# Instrument_Cluster.net
KiCad netlist of a schematic drawn in EAGLE
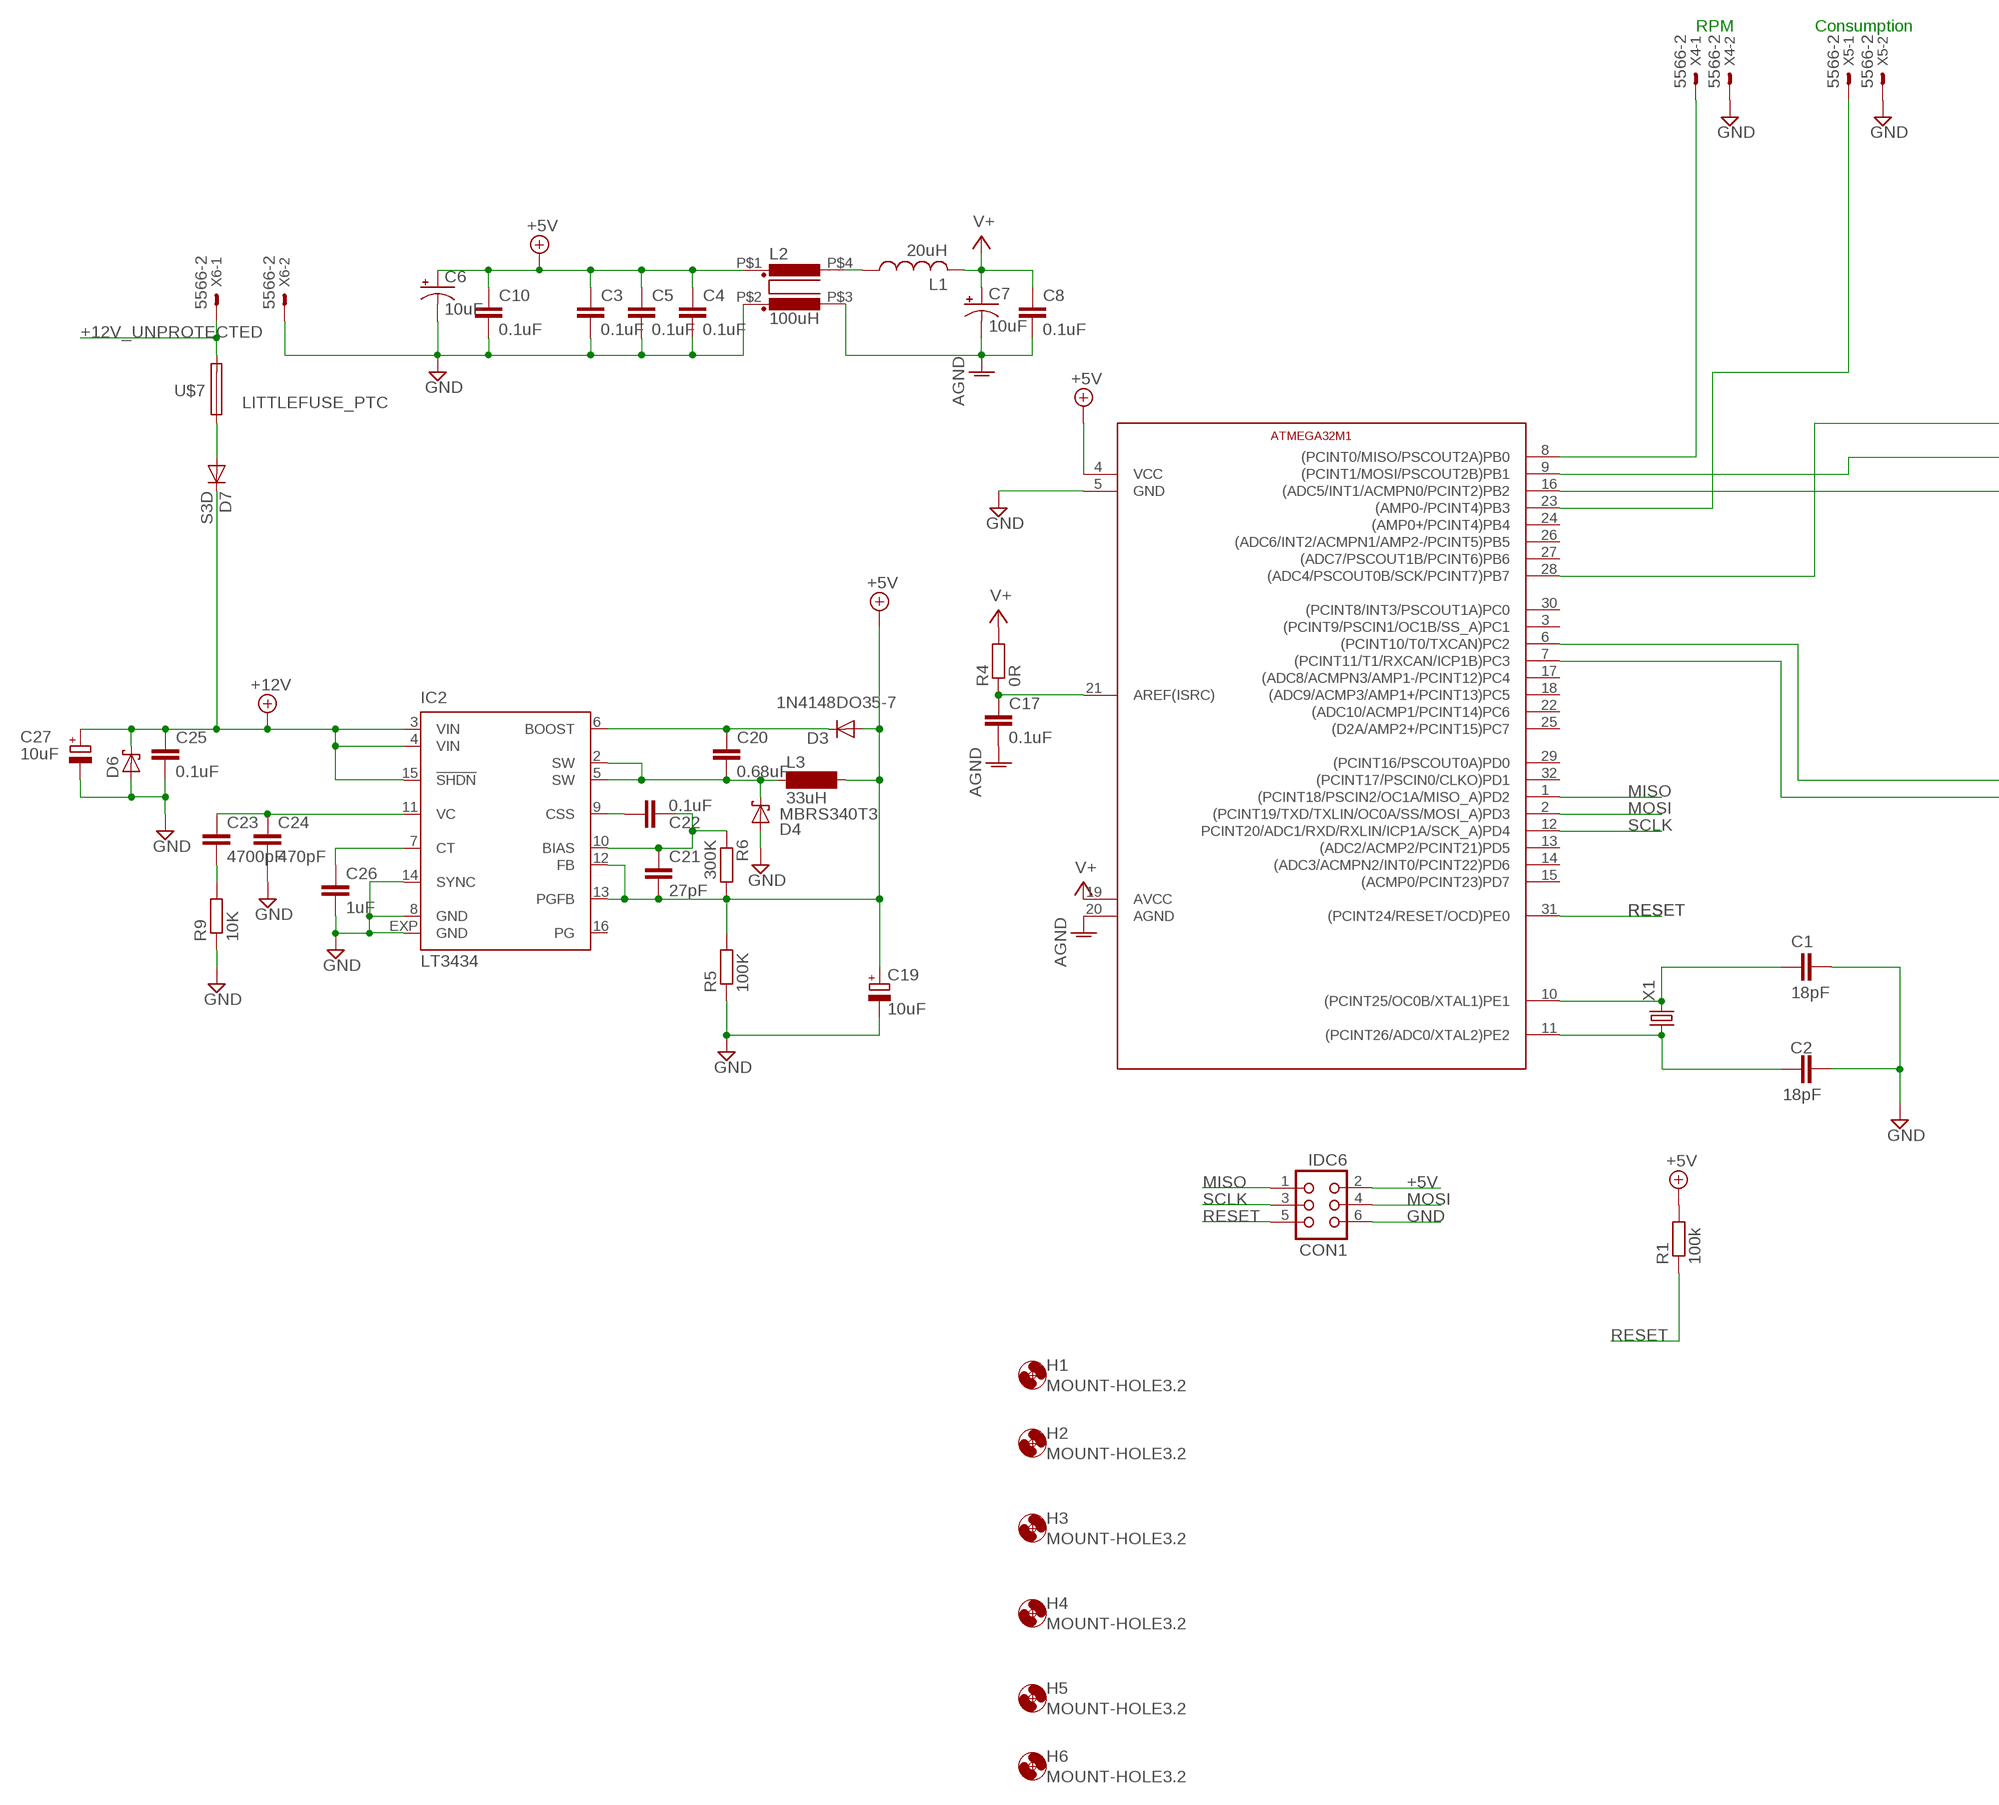
[diagram p0: schematic, sheet 1, part 1 of 2]
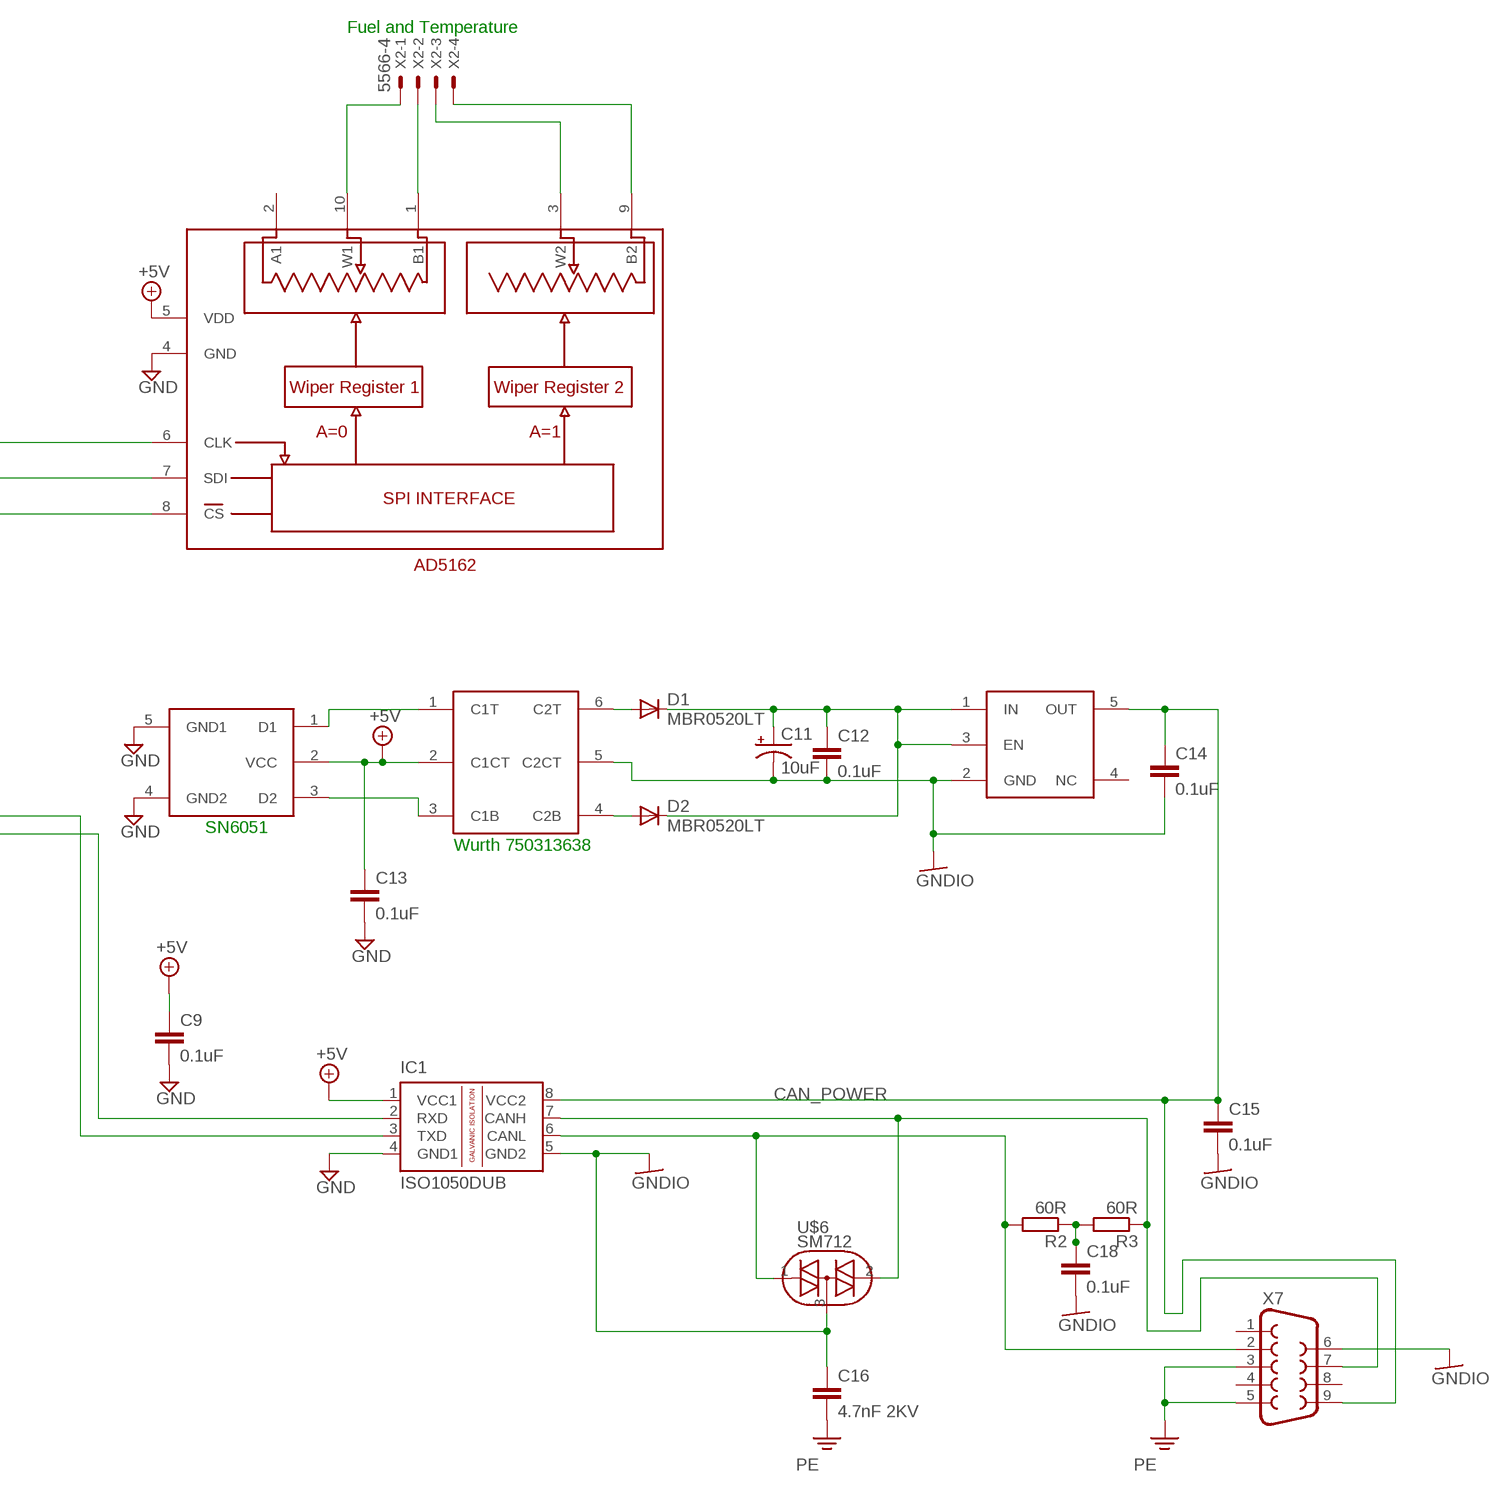
[diagram p1: schematic, sheet 1, part 2 of 2]

(export (version "E")
  (design (tool "Eeschema 10.0.6"))
  (components
    (comp (ref "C1")
      (value "18pF")
      (footprint "eagle-import:C0805")
      (libsource (lib "eagle-import") (part "C-EUC0805"))
    )
    (comp (ref "C2")
      (value "18pF")
      (footprint "eagle-import:C0805")
      (libsource (lib "eagle-import") (part "C-EUC0805"))
    )
    (comp (ref "C3")
      (value "0.1uF")
      (footprint "eagle-import:C0805")
      (libsource (lib "eagle-import") (part "C-EUC0805"))
    )
    (comp (ref "C4")
      (value "0.1uF")
      (footprint "eagle-import:C0805")
      (libsource (lib "eagle-import") (part "C-EUC0805"))
    )
    (comp (ref "C5")
      (value "0.1uF")
      (footprint "eagle-import:C0805")
      (libsource (lib "eagle-import") (part "C-EUC0805"))
    )
    (comp (ref "C6")
      (value "10uF")
      (footprint "eagle-import:SMC_C")
      (libsource (lib "eagle-import") (part "CPOL-USSMCC"))
    )
    (comp (ref "C7")
      (value "10uF")
      (footprint "eagle-import:SMC_C")
      (libsource (lib "eagle-import") (part "CPOL-USSMCC"))
    )
    (comp (ref "C8")
      (value "0.1uF")
      (footprint "eagle-import:C0805")
      (libsource (lib "eagle-import") (part "C-EUC0805"))
    )
    (comp (ref "C9")
      (value "0.1uF")
      (footprint "eagle-import:C0805")
      (libsource (lib "eagle-import") (part "C-EUC0805"))
    )
    (comp (ref "C10")
      (value "0.1uF")
      (footprint "eagle-import:C0805")
      (libsource (lib "eagle-import") (part "C-EUC0805"))
    )
    (comp (ref "C11")
      (value "10uF")
      (footprint "eagle-import:SMC_D")
      (libsource (lib "eagle-import") (part "CPOL-USSMCD"))
    )
    (comp (ref "C12")
      (value "0.1uF")
      (footprint "eagle-import:C0603")
      (libsource (lib "eagle-import") (part "C-EUC0603"))
    )
    (comp (ref "C13")
      (value "0.1uF")
      (footprint "eagle-import:C1206")
      (libsource (lib "eagle-import") (part "C-EUC1206"))
    )
    (comp (ref "C14")
      (value "0.1uF")
      (footprint "eagle-import:C1206")
      (libsource (lib "eagle-import") (part "C-EUC1206"))
    )
    (comp (ref "C15")
      (value "0.1uF")
      (footprint "eagle-import:C0603")
      (libsource (lib "eagle-import") (part "C-EUC0603"))
    )
    (comp (ref "C16")
      (value "4.7nF 2KV")
      (footprint "eagle-import:C1206")
      (libsource (lib "eagle-import") (part "C-EUC1206"))
    )
    (comp (ref "C17")
      (value "0.1uF")
      (footprint "eagle-import:C0805")
      (libsource (lib "eagle-import") (part "C-EUC0805"))
    )
    (comp (ref "C18")
      (value "0.1uF")
      (footprint "eagle-import:C1206")
      (libsource (lib "eagle-import") (part "C-EUC1206"))
    )
    (comp (ref "C19")
      (value "10uF")
      (footprint "eagle-import:SMC_D")
      (libsource (lib "eagle-import") (part "CPOL-EUSMCD"))
    )
    (comp (ref "C20")
      (value "0.68uF")
      (footprint "eagle-import:C0603")
      (libsource (lib "eagle-import") (part "C-EUC0603"))
    )
    (comp (ref "C21")
      (value "27pF")
      (footprint "eagle-import:C0603")
      (libsource (lib "eagle-import") (part "C-EUC0603"))
    )
    (comp (ref "C22")
      (value "0.1uF")
      (footprint "eagle-import:C0603")
      (libsource (lib "eagle-import") (part "C-EUC0603"))
    )
    (comp (ref "C23")
      (value "4700pF")
      (footprint "eagle-import:C0603")
      (libsource (lib "eagle-import") (part "C-EUC0603"))
    )
    (comp (ref "C24")
      (value "470pF")
      (footprint "eagle-import:C0603")
      (libsource (lib "eagle-import") (part "C-EUC0603"))
    )
    (comp (ref "C25")
      (value "0.1uF")
      (footprint "eagle-import:C0603")
      (libsource (lib "eagle-import") (part "C-EUC0603"))
    )
    (comp (ref "C26")
      (value "1uF")
      (footprint "eagle-import:C0603")
      (libsource (lib "eagle-import") (part "C-EUC0603"))
    )
    (comp (ref "C27")
      (value "10uF")
      (footprint "eagle-import:SMC_D")
      (libsource (lib "eagle-import") (part "CPOL-EUSMCD"))
    )
    (comp (ref "CON1")
      (value "IDC6")
      (footprint "eagle-import:CON06")
      (libsource (lib "eagle-import") (part "CON06"))
    )
    (comp (ref "D1")
      (value "MBR0520LT")
      (footprint "eagle-import:SOD123")
      (libsource (lib "eagle-import") (part "MBR0520LT"))
    )
    (comp (ref "D2")
      (value "MBR0520LT")
      (footprint "eagle-import:SOD123")
      (libsource (lib "eagle-import") (part "MBR0520LT"))
    )
    (comp (ref "D3")
      (value "1N4148DO35-7")
      (footprint "eagle-import:DO35-7")
      (libsource (lib "eagle-import") (part "1N4148DO35-7"))
    )
    (comp (ref "D4")
      (value "MBRS340T3")
      (footprint "eagle-import:SMC")
      (libsource (lib "eagle-import") (part "MBRS30T34"))
    )
    (comp (ref "D6")
      (value "SCHOTTKY-DIODESMC")
      (footprint "eagle-import:SMC")
      (libsource (lib "eagle-import") (part "SCHOTTKY-DIODESMC"))
    )
    (comp (ref "D7")
      (value "S3D")
      (footprint "eagle-import:SMC")
      (libsource (lib "eagle-import") (part "DIODE-SMC"))
    )
    (comp (ref "H1")
      (value "MOUNT-HOLE3.2")
      (footprint "eagle-import:3,2")
      (libsource (lib "eagle-import") (part "MOUNT-HOLE3.2"))
    )
    (comp (ref "H2")
      (value "MOUNT-HOLE3.2")
      (footprint "eagle-import:3,2")
      (libsource (lib "eagle-import") (part "MOUNT-HOLE3.2"))
    )
    (comp (ref "H3")
      (value "MOUNT-HOLE3.2")
      (footprint "eagle-import:3,2")
      (libsource (lib "eagle-import") (part "MOUNT-HOLE3.2"))
    )
    (comp (ref "H4")
      (value "MOUNT-HOLE3.2")
      (footprint "eagle-import:3,2")
      (libsource (lib "eagle-import") (part "MOUNT-HOLE3.2"))
    )
    (comp (ref "H5")
      (value "MOUNT-HOLE3.2")
      (footprint "eagle-import:3,2")
      (libsource (lib "eagle-import") (part "MOUNT-HOLE3.2"))
    )
    (comp (ref "H6")
      (value "MOUNT-HOLE3.2")
      (footprint "eagle-import:3,2")
      (libsource (lib "eagle-import") (part "MOUNT-HOLE3.2"))
    )
    (comp (ref "IC1")
      (value "ISO1050DUB")
      (footprint "eagle-import:DUB-R-PDSO-G8")
      (fields (field (name "MPN") "ISO1050DUBR"))
      (libsource (lib "eagle-import") (part "ISO1050DUB"))
    )
    (comp (ref "IC2")
      (value "LT3434")
      (footprint "eagle-import:TSSOP16EXP")
      (fields (field (name "MPN") "LT3434EFE#PBF"))
      (libsource (lib "eagle-import") (part "LT3434"))
    )
    (comp (ref "L1")
      (value "20uH")
      (footprint "eagle-import:L3216C")
      (libsource (lib "eagle-import") (part "L-USL3216C"))
    )
    (comp (ref "L2")
      (value "100uH")
      (footprint "eagle-import:CHIP")
      (libsource (lib "eagle-import") (part "R1003U"))
    )
    (comp (ref "L3")
      (value "33uH")
      (footprint "eagle-import:MS85")
      (libsource (lib "eagle-import") (part "MS85"))
    )
    (comp (ref "R1")
      (value "100k")
      (footprint "eagle-import:R0603")
      (libsource (lib "eagle-import") (part "R-EU_R0603"))
    )
    (comp (ref "R2")
      (value "60R")
      (footprint "eagle-import:R0603")
      (libsource (lib "eagle-import") (part "R-EU_R0603"))
    )
    (comp (ref "R3")
      (value "60R")
      (footprint "eagle-import:R0603")
      (libsource (lib "eagle-import") (part "R-EU_R0603"))
    )
    (comp (ref "R4")
      (value "0R")
      (footprint "eagle-import:R0603")
      (libsource (lib "eagle-import") (part "R-EU_R0603"))
    )
    (comp (ref "R5")
      (value "100K")
      (footprint "eagle-import:R0603")
      (libsource (lib "eagle-import") (part "R-EU_R0603"))
    )
    (comp (ref "R6")
      (value "300K")
      (footprint "eagle-import:R0603")
      (libsource (lib "eagle-import") (part "R-EU_R0603"))
    )
    (comp (ref "R9")
      (value "10K")
      (footprint "eagle-import:R0603")
      (libsource (lib "eagle-import") (part "R-EU_R0603"))
    )
    (comp (ref "U$1")
      (value "ATMEGA32M1")
      (footprint "eagle-import:TQFP32-08")
      (libsource (lib "eagle-import") (part "ATMEGA32M1"))
    )
    (comp (ref "U$2")
      (value "AD5162")
      (footprint "eagle-import:MSOP10")
      (libsource (lib "eagle-import") (part "AD5162"))
    )
    (comp (ref "U$3")
      (value "SN6501")
      (footprint "eagle-import:SOT23-DBV")
      (libsource (lib "eagle-import") (part "SN6501"))
    )
    (comp (ref "U$4")
      (value "WURTHWURTH")
      (footprint "eagle-import:TSOT23-6_DDC")
      (libsource (lib "eagle-import") (part "WURTHWURTH"))
    )
    (comp (ref "U$5")
      (value "TPS76350")
      (footprint "eagle-import:SOT23-DBV")
      (libsource (lib "eagle-import") (part "TPS76350"))
    )
    (comp (ref "U$6")
      (value "SM712")
      (footprint "eagle-import:SOT23")
      (libsource (lib "eagle-import") (part "SM712"))
    )
    (comp (ref "U$7")
      (value "LITTLEFUSE_PTC")
      (footprint "eagle-import:1812")
      (libsource (lib "eagle-import") (part "LITTLEFUSE_PTC"))
    )
    (comp (ref "X1")
      (value "CSM-7X-DU")
      (footprint "eagle-import:CSM-7X-DU")
      (libsource (lib "eagle-import") (part "CSM-7X-DU"))
    )
    (comp (ref "X2")
      (value "5566-4")
      (footprint "eagle-import:5566-4")
      (libsource (lib "eagle-import") (part "5566-4"))
    )
    (comp (ref "X4")
      (value "5566-2")
      (footprint "eagle-import:5566-2")
      (libsource (lib "eagle-import") (part "5566-2"))
    )
    (comp (ref "X5")
      (value "5566-2")
      (footprint "eagle-import:5566-2")
      (libsource (lib "eagle-import") (part "5566-2"))
    )
    (comp (ref "X6")
      (value "5566-2")
      (footprint "eagle-import:5566-2")
      (libsource (lib "eagle-import") (part "5566-2"))
    )
    (comp (ref "X7")
      (value "F09H")
      (footprint "eagle-import:F09H")
      (libsource (lib "eagle-import") (part "F09H"))
    )
  )
  (nets
    (net (code "1") (name "+5V") (class "Default")
      (node (ref "C10") (pin "1") (pinfunction "1_1") (pintype "passive"))
      (node (ref "C13") (pin "1") (pinfunction "1_1") (pintype "passive"))
      (node (ref "C19") (pin "+") (pinfunction "+_+") (pintype "passive"))
      (node (ref "C21") (pin "2") (pinfunction "2_2") (pintype "passive"))
      (node (ref "C3") (pin "1") (pinfunction "1_1") (pintype "passive"))
      (node (ref "C4") (pin "1") (pinfunction "1_1") (pintype "passive"))
      (node (ref "C5") (pin "1") (pinfunction "1_1") (pintype "passive"))
      (node (ref "C6") (pin "+") (pinfunction "+_+") (pintype "passive"))
      (node (ref "C9") (pin "1") (pinfunction "1_1") (pintype "passive"))
      (node (ref "CON1") (pin "2") (pinfunction "2_2") (pintype "passive"))
      (node (ref "D3") (pin "A") (pinfunction "A_A") (pintype "passive"))
      (node (ref "IC1") (pin "1") (pinfunction "VCC1_1") (pintype "input"))
      (node (ref "IC2") (pin "12") (pinfunction "FB_12") (pintype "input"))
      (node (ref "IC2") (pin "13") (pinfunction "PGFB_13") (pintype "input"))
      (node (ref "L2") (pin "P$1") (pinfunction "1_P$1") (pintype "passive"))
      (node (ref "L3") (pin "2") (pinfunction "2_2") (pintype "passive"))
      (node (ref "R1") (pin "2") (pinfunction "2_2") (pintype "passive"))
      (node (ref "R5") (pin "2") (pinfunction "2_2") (pintype "passive"))
      (node (ref "R6") (pin "2") (pinfunction "2_2") (pintype "passive"))
      (node (ref "U$1") (pin "4") (pinfunction "VCC_4") (pintype "power_in"))
      (node (ref "U$2") (pin "5") (pinfunction "VDD_5") (pintype "bidirectional"))
      (node (ref "U$3") (pin "2") (pinfunction "VCC_2") (pintype "bidirectional"))
      (node (ref "U$4") (pin "2") (pinfunction "C1CT_2") (pintype "bidirectional"))
    )
    (net (code "2") (name "+12V") (class "Default")
      (node (ref "C25") (pin "1") (pinfunction "1_1") (pintype "passive"))
      (node (ref "C27") (pin "+") (pinfunction "+_+") (pintype "passive"))
      (node (ref "D6") (pin "C") (pinfunction "C_C") (pintype "passive"))
      (node (ref "D7") (pin "C") (pinfunction "C_C") (pintype "passive"))
      (node (ref "IC2") (pin "15") (pinfunction "~{SHDN}_15") (pintype "input"))
      (node (ref "IC2") (pin "3") (pinfunction "VIN_3") (pintype "input"))
      (node (ref "IC2") (pin "4") (pinfunction "VIN_4") (pintype "input"))
    )
    (net (code "3") (name "/+12V_UNPROTECTED") (class "Default")
      (node (ref "U$7") (pin "P$2") (pinfunction "2_P$2") (pintype "passive"))
      (node (ref "X6") (pin "1") (pinfunction "S_1") (pintype "passive"))
    )
    (net (code "4") (name "/CAN_POWER") (class "Default")
      (node (ref "C14") (pin "1") (pinfunction "1_1") (pintype "passive"))
      (node (ref "C15") (pin "1") (pinfunction "1_1") (pintype "passive"))
      (node (ref "IC1") (pin "8") (pinfunction "VCC2_8") (pintype "input"))
      (node (ref "U$5") (pin "5") (pinfunction "OUT_5") (pintype "bidirectional"))
      (node (ref "X7") (pin "9") (pinfunction "9_9") (pintype "passive"))
    )
    (net (code "5") (name "/MISO") (class "Default")
      (node (ref "CON1") (pin "1") (pinfunction "1_1") (pintype "passive"))
      (node (ref "U$1") (pin "1") (pinfunction "(PCINT18/PSCIN2/OC1A/MISO_A)PD2_1") (pintype "bidirectional"))
    )
    (net (code "6") (name "/MOSI") (class "Default")
      (node (ref "CON1") (pin "4") (pinfunction "4_4") (pintype "passive"))
      (node (ref "U$1") (pin "2") (pinfunction "(PCINT19/TXD/TXLIN/OC0A/SS/MOSI_A)PD3_2") (pintype "bidirectional"))
    )
    (net (code "7") (name "/RESET") (class "Default")
      (node (ref "CON1") (pin "5") (pinfunction "5_5") (pintype "passive"))
      (node (ref "R1") (pin "1") (pinfunction "1_1") (pintype "passive"))
      (node (ref "U$1") (pin "31") (pinfunction "(PCINT24/RESET/OCD)PE0_31") (pintype "bidirectional"))
    )
    (net (code "8") (name "/SCLK") (class "Default")
      (node (ref "CON1") (pin "3") (pinfunction "3_3") (pintype "passive"))
      (node (ref "U$1") (pin "12") (pinfunction "PCINT20/ADC1/RXD/RXLIN/ICP1A/SCK_A)PD4_12") (pintype "bidirectional"))
    )
    (net (code "9") (name "AGND") (class "Default")
      (node (ref "C17") (pin "2") (pinfunction "2_2") (pintype "passive"))
      (node (ref "C7") (pin "-") (pinfunction "-_-") (pintype "passive"))
      (node (ref "C8") (pin "2") (pinfunction "2_2") (pintype "passive"))
      (node (ref "L2") (pin "P$3") (pinfunction "4_P$3") (pintype "passive"))
      (node (ref "U$1") (pin "20") (pinfunction "AGND_20") (pintype "power_in"))
    )
    (net (code "10") (name "GND") (class "Default")
      (node (ref "C1") (pin "1") (pinfunction "1_1") (pintype "passive"))
      (node (ref "C10") (pin "2") (pinfunction "2_2") (pintype "passive"))
      (node (ref "C13") (pin "2") (pinfunction "2_2") (pintype "passive"))
      (node (ref "C19") (pin "-") (pinfunction "-_-") (pintype "passive"))
      (node (ref "C2") (pin "2") (pinfunction "2_2") (pintype "passive"))
      (node (ref "C24") (pin "2") (pinfunction "2_2") (pintype "passive"))
      (node (ref "C25") (pin "2") (pinfunction "2_2") (pintype "passive"))
      (node (ref "C26") (pin "2") (pinfunction "2_2") (pintype "passive"))
      (node (ref "C27") (pin "-") (pinfunction "-_-") (pintype "passive"))
      (node (ref "C3") (pin "2") (pinfunction "2_2") (pintype "passive"))
      (node (ref "C4") (pin "2") (pinfunction "2_2") (pintype "passive"))
      (node (ref "C5") (pin "2") (pinfunction "2_2") (pintype "passive"))
      (node (ref "C6") (pin "-") (pinfunction "-_-") (pintype "passive"))
      (node (ref "C9") (pin "2") (pinfunction "2_2") (pintype "passive"))
      (node (ref "CON1") (pin "6") (pinfunction "6_6") (pintype "passive"))
      (node (ref "D4") (pin "A") (pinfunction "A_A") (pintype "passive"))
      (node (ref "D6") (pin "A") (pinfunction "A_A") (pintype "passive"))
      (node (ref "IC1") (pin "4") (pinfunction "GND1_4") (pintype "input"))
      (node (ref "IC2") (pin "14") (pinfunction "SYNC_14") (pintype "input"))
      (node (ref "IC2") (pin "8") (pinfunction "GND_8") (pintype "power_in"))
      (node (ref "IC2") (pin "EXP") (pinfunction "GND_EXP") (pintype "power_in"))
      (node (ref "L2") (pin "P$2") (pinfunction "3_P$2") (pintype "passive"))
      (node (ref "R5") (pin "1") (pinfunction "1_1") (pintype "passive"))
      (node (ref "R9") (pin "1") (pinfunction "1_1") (pintype "passive"))
      (node (ref "U$1") (pin "5") (pinfunction "GND_5") (pintype "power_in"))
      (node (ref "U$2") (pin "4") (pinfunction "GND_4") (pintype "bidirectional"))
      (node (ref "U$3") (pin "4") (pinfunction "GND2_4") (pintype "bidirectional"))
      (node (ref "U$3") (pin "5") (pinfunction "GND1_5") (pintype "bidirectional"))
      (node (ref "X4") (pin "2") (pinfunction "S_2") (pintype "passive"))
      (node (ref "X5") (pin "2") (pinfunction "S_2") (pintype "passive"))
      (node (ref "X6") (pin "2") (pinfunction "S_2") (pintype "passive"))
    )
    (net (code "11") (name "GNDIO") (class "Default")
      (node (ref "C11") (pin "-") (pinfunction "-_-") (pintype "passive"))
      (node (ref "C12") (pin "2") (pinfunction "2_2") (pintype "passive"))
      (node (ref "C14") (pin "2") (pinfunction "2_2") (pintype "passive"))
      (node (ref "C15") (pin "2") (pinfunction "2_2") (pintype "passive"))
      (node (ref "C16") (pin "1") (pinfunction "1_1") (pintype "passive"))
      (node (ref "C18") (pin "2") (pinfunction "2_2") (pintype "passive"))
      (node (ref "IC1") (pin "5") (pinfunction "GND2_5") (pintype "input"))
      (node (ref "U$4") (pin "5") (pinfunction "C2CT_5") (pintype "bidirectional"))
      (node (ref "U$5") (pin "2") (pinfunction "GND_2") (pintype "bidirectional"))
      (node (ref "U$6") (pin "3") (pinfunction "T2_3") (pintype "passive"))
      (node (ref "X7") (pin "6") (pinfunction "6_6") (pintype "passive"))
    )
    (net (code "12") (name "Net-(C18-Pad1)") (class "Default")
      (node (ref "C18") (pin "1") (pinfunction "1_1") (pintype "passive"))
      (node (ref "R2") (pin "1") (pinfunction "1_1") (pintype "passive"))
      (node (ref "R3") (pin "2") (pinfunction "2_2") (pintype "passive"))
    )
    (net (code "13") (name "Net-(C20-Pad2)") (class "Default")
      (node (ref "C20") (pin "2") (pinfunction "2_2") (pintype "passive"))
      (node (ref "D4") (pin "C") (pinfunction "C_C") (pintype "passive"))
      (node (ref "IC2") (pin "2") (pinfunction "SW_2") (pintype "output"))
      (node (ref "IC2") (pin "5") (pinfunction "SW_5") (pintype "passive"))
      (node (ref "L3") (pin "1") (pinfunction "1_1") (pintype "passive"))
    )
    (net (code "14") (name "Net-(C23-Pad2)") (class "Default")
      (node (ref "C23") (pin "2") (pinfunction "2_2") (pintype "passive"))
      (node (ref "R9") (pin "2") (pinfunction "2_2") (pintype "passive"))
    )
    (net (code "15") (name "Net-(IC1-CANH)") (class "Default")
      (node (ref "IC1") (pin "7") (pinfunction "CANH_7") (pintype "input"))
      (node (ref "R3") (pin "1") (pinfunction "1_1") (pintype "passive"))
      (node (ref "U$6") (pin "2") (pinfunction "T3_2") (pintype "passive"))
      (node (ref "X7") (pin "7") (pinfunction "7_7") (pintype "passive"))
    )
    (net (code "16") (name "Net-(IC1-CANL)") (class "Default")
      (node (ref "IC1") (pin "6") (pinfunction "CANL_6") (pintype "input"))
      (node (ref "R2") (pin "2") (pinfunction "2_2") (pintype "passive"))
      (node (ref "U$6") (pin "1") (pinfunction "T1_1") (pintype "passive"))
      (node (ref "X7") (pin "2") (pinfunction "2_2") (pintype "passive"))
    )
    (net (code "17") (name "Net-(IC1-RXD)") (class "Default")
      (node (ref "IC1") (pin "2") (pinfunction "RXD_2") (pintype "input"))
      (node (ref "U$1") (pin "7") (pinfunction "(PCINT11/T1/RXCAN/ICP1B)PC3_7") (pintype "bidirectional"))
    )
    (net (code "18") (name "Net-(IC1-TXD)") (class "Default")
      (node (ref "IC1") (pin "3") (pinfunction "TXD_3") (pintype "input"))
      (node (ref "U$1") (pin "6") (pinfunction "(PCINT10/T0/TXCAN)PC2_6") (pintype "bidirectional"))
    )
    (net (code "19") (name "Net-(IC2-BIAS)") (class "Default")
      (node (ref "C21") (pin "1") (pinfunction "1_1") (pintype "passive"))
      (node (ref "C22") (pin "2") (pinfunction "2_2") (pintype "passive"))
      (node (ref "IC2") (pin "10") (pinfunction "BIAS_10") (pintype "input"))
      (node (ref "R6") (pin "1") (pinfunction "1_1") (pintype "passive"))
    )
    (net (code "20") (name "Net-(IC2-BOOST)") (class "Default")
      (node (ref "C20") (pin "1") (pinfunction "1_1") (pintype "passive"))
      (node (ref "D3") (pin "C") (pinfunction "C_C") (pintype "passive"))
      (node (ref "IC2") (pin "6") (pinfunction "BOOST_6") (pintype "input"))
    )
    (net (code "21") (name "Net-(IC2-CSS)") (class "Default")
      (node (ref "C22") (pin "1") (pinfunction "1_1") (pintype "passive"))
      (node (ref "IC2") (pin "9") (pinfunction "CSS_9") (pintype "input"))
    )
    (net (code "22") (name "Net-(IC2-CT)") (class "Default")
      (node (ref "C26") (pin "1") (pinfunction "1_1") (pintype "passive"))
      (node (ref "IC2") (pin "7") (pinfunction "CT_7") (pintype "passive"))
    )
    (net (code "23") (name "Net-(IC2-VC)") (class "Default")
      (node (ref "C23") (pin "1") (pinfunction "1_1") (pintype "passive"))
      (node (ref "C24") (pin "1") (pinfunction "1_1") (pintype "passive"))
      (node (ref "IC2") (pin "11") (pinfunction "VC_11") (pintype "passive"))
    )
    (net (code "24") (name "Net-(L2-2)") (class "Default")
      (node (ref "L1") (pin "1") (pinfunction "1_1") (pintype "passive"))
      (node (ref "L2") (pin "P$4") (pinfunction "2_P$4") (pintype "passive"))
    )
    (net (code "25") (name "Net-(U$1-(ADC4{slash}PSCOUT0B{slash}SCK{slash}PCINT7)PB7)") (class "Default")
      (node (ref "U$1") (pin "28") (pinfunction "(ADC4/PSCOUT0B/SCK/PCINT7)PB7_28") (pintype "bidirectional"))
      (node (ref "U$2") (pin "6") (pinfunction "CLK_6") (pintype "bidirectional"))
    )
    (net (code "26") (name "Net-(U$1-(ADC5{slash}INT1{slash}ACMPN0{slash}PCINT2)PB2)") (class "Default")
      (node (ref "U$1") (pin "16") (pinfunction "(ADC5/INT1/ACMPN0/PCINT2)PB2_16") (pintype "bidirectional"))
      (node (ref "U$2") (pin "8") (pinfunction "CS_8") (pintype "bidirectional"))
    )
    (net (code "27") (name "Net-(U$1-(AMP0-{slash}PCINT4)PB3)") (class "Default")
      (node (ref "U$1") (pin "23") (pinfunction "(AMP0-/PCINT4)PB3_23") (pintype "bidirectional"))
      (node (ref "X5") (pin "1") (pinfunction "S_1") (pintype "passive"))
    )
    (net (code "28") (name "Net-(U$1-(PCINT0{slash}MISO{slash}PSCOUT2A)PB0)") (class "Default")
      (node (ref "U$1") (pin "8") (pinfunction "(PCINT0/MISO/PSCOUT2A)PB0_8") (pintype "bidirectional"))
      (node (ref "X4") (pin "1") (pinfunction "S_1") (pintype "passive"))
    )
    (net (code "29") (name "Net-(U$1-(PCINT1{slash}MOSI{slash}PSCOUT2B)PB1)") (class "Default")
      (node (ref "U$1") (pin "9") (pinfunction "(PCINT1/MOSI/PSCOUT2B)PB1_9") (pintype "bidirectional"))
      (node (ref "U$2") (pin "7") (pinfunction "SDI_7") (pintype "bidirectional"))
    )
    (net (code "30") (name "Net-(U$1-(PCINT25{slash}OC0B{slash}XTAL1)PE1)") (class "Default")
      (node (ref "C1") (pin "2") (pinfunction "2_2") (pintype "passive"))
      (node (ref "U$1") (pin "10") (pinfunction "(PCINT25/OC0B/XTAL1)PE1_10") (pintype "bidirectional"))
      (node (ref "X1") (pin "2") (pinfunction "2_2") (pintype "passive"))
    )
    (net (code "31") (name "Net-(U$1-(PCINT26{slash}ADC0{slash}XTAL2)PE2)") (class "Default")
      (node (ref "C2") (pin "1") (pinfunction "1_1") (pintype "passive"))
      (node (ref "U$1") (pin "11") (pinfunction "(PCINT26/ADC0/XTAL2)PE2_11") (pintype "bidirectional"))
      (node (ref "X1") (pin "1") (pinfunction "1_1") (pintype "passive"))
    )
    (net (code "32") (name "Net-(U$1-AREF(ISRC))") (class "Default")
      (node (ref "C17") (pin "1") (pinfunction "1_1") (pintype "passive"))
      (node (ref "R4") (pin "1") (pinfunction "1_1") (pintype "passive"))
      (node (ref "U$1") (pin "21") (pinfunction "AREF(ISRC)_21") (pintype "power_in"))
    )
    (net (code "33") (name "Net-(U$2-B1)") (class "Default")
      (node (ref "U$2") (pin "1") (pinfunction "B1_1") (pintype "bidirectional"))
      (node (ref "X2") (pin "2") (pinfunction "S_2") (pintype "passive"))
    )
    (net (code "34") (name "Net-(U$2-B2)") (class "Default")
      (node (ref "U$2") (pin "9") (pinfunction "B2_9") (pintype "bidirectional"))
      (node (ref "X2") (pin "4") (pinfunction "S_4") (pintype "passive"))
    )
    (net (code "35") (name "Net-(U$2-W1)") (class "Default")
      (node (ref "U$2") (pin "10") (pinfunction "W1_10") (pintype "bidirectional"))
      (node (ref "X2") (pin "1") (pinfunction "S_1") (pintype "passive"))
    )
    (net (code "36") (name "Net-(U$2-W2)") (class "Default")
      (node (ref "U$2") (pin "3") (pinfunction "W2_3") (pintype "bidirectional"))
      (node (ref "X2") (pin "3") (pinfunction "S_3") (pintype "passive"))
    )
    (net (code "37") (name "Net-(U$3-D1)") (class "Default")
      (node (ref "U$3") (pin "1") (pinfunction "D1_1") (pintype "bidirectional"))
      (node (ref "U$4") (pin "1") (pinfunction "C1T_1") (pintype "bidirectional"))
    )
    (net (code "38") (name "Net-(U$3-D2)") (class "Default")
      (node (ref "U$3") (pin "3") (pinfunction "D2_3") (pintype "bidirectional"))
      (node (ref "U$4") (pin "3") (pinfunction "C1B_3") (pintype "bidirectional"))
    )
    (net (code "39") (name "Net-(U$4-C2B)") (class "Default")
      (node (ref "D2") (pin "A") (pinfunction "A_A") (pintype "passive"))
      (node (ref "U$4") (pin "4") (pinfunction "C2B_4") (pintype "bidirectional"))
    )
    (net (code "40") (name "Net-(U$4-C2T)") (class "Default")
      (node (ref "D1") (pin "A") (pinfunction "A_A") (pintype "passive"))
      (node (ref "U$4") (pin "6") (pinfunction "C2T_6") (pintype "bidirectional"))
    )
    (net (code "41") (name "Net-(U$5-EN)") (class "Default")
      (node (ref "C11") (pin "+") (pinfunction "+_+") (pintype "passive"))
      (node (ref "C12") (pin "1") (pinfunction "1_1") (pintype "passive"))
      (node (ref "D1") (pin "C") (pinfunction "C_C") (pintype "passive"))
      (node (ref "D2") (pin "C") (pinfunction "C_C") (pintype "passive"))
      (node (ref "U$5") (pin "1") (pinfunction "IN_1") (pintype "bidirectional"))
      (node (ref "U$5") (pin "3") (pinfunction "EN_3") (pintype "bidirectional"))
    )
    (net (code "42") (name "Net-(U$7-1)") (class "Default")
      (node (ref "D7") (pin "A") (pinfunction "A_A") (pintype "passive"))
      (node (ref "U$7") (pin "P$1") (pinfunction "1_P$1") (pintype "passive"))
    )
    (net (code "43") (name "PE") (class "Default")
      (node (ref "C16") (pin "2") (pinfunction "2_2") (pintype "passive"))
      (node (ref "X7") (pin "3") (pinfunction "3_3") (pintype "passive"))
      (node (ref "X7") (pin "5") (pinfunction "5_5") (pintype "passive"))
    )
    (net (code "44") (name "V+") (class "Default")
      (node (ref "C7") (pin "+") (pinfunction "+_+") (pintype "passive"))
      (node (ref "C8") (pin "1") (pinfunction "1_1") (pintype "passive"))
      (node (ref "L1") (pin "2") (pinfunction "2_2") (pintype "passive"))
      (node (ref "R4") (pin "2") (pinfunction "2_2") (pintype "passive"))
      (node (ref "U$1") (pin "19") (pinfunction "AVCC_19") (pintype "power_in"))
    )
    (net (code "45") (name "unconnected-(IC2-PG-Pad16)") (class "Default")
      (node (ref "IC2") (pin "16") (pinfunction "PG_16") (pintype "open_collector"))
    )
    (net (code "46") (name "unconnected-(U$1-(ACMP0{slash}PCINT23)PD7-Pad15)") (class "Default")
      (node (ref "U$1") (pin "15") (pinfunction "(ACMP0/PCINT23)PD7_15") (pintype "bidirectional"))
    )
    (net (code "47") (name "unconnected-(U$1-(ADC2{slash}ACMP2{slash}PCINT21)PD5-Pad13)") (class "Default")
      (node (ref "U$1") (pin "13") (pinfunction "(ADC2/ACMP2/PCINT21)PD5_13") (pintype "bidirectional"))
    )
    (net (code "48") (name "unconnected-(U$1-(ADC3{slash}ACMPN2{slash}INT0{slash}PCINT22)PD6-Pad14)") (class "Default")
      (node (ref "U$1") (pin "14") (pinfunction "(ADC3/ACMPN2/INT0/PCINT22)PD6_14") (pintype "bidirectional"))
    )
    (net (code "49") (name "unconnected-(U$1-(ADC6{slash}INT2{slash}ACMPN1{slash}AMP2-{slash}PCINT5)PB5-Pad26)") (class "Default")
      (node (ref "U$1") (pin "26") (pinfunction "(ADC6/INT2/ACMPN1/AMP2-/PCINT5)PB5_26") (pintype "bidirectional"))
    )
    (net (code "50") (name "unconnected-(U$1-(ADC7{slash}PSCOUT1B{slash}PCINT6)PB6-Pad27)") (class "Default")
      (node (ref "U$1") (pin "27") (pinfunction "(ADC7/PSCOUT1B/PCINT6)PB6_27") (pintype "bidirectional"))
    )
    (net (code "51") (name "unconnected-(U$1-(ADC8{slash}ACMPN3{slash}AMP1-{slash}PCINT12)PC4-Pad17)") (class "Default")
      (node (ref "U$1") (pin "17") (pinfunction "(ADC8/ACMPN3/AMP1-/PCINT12)PC4_17") (pintype "bidirectional"))
    )
    (net (code "52") (name "unconnected-(U$1-(ADC9{slash}ACMP3{slash}AMP1+{slash}PCINT13)PC5-Pad18)") (class "Default")
      (node (ref "U$1") (pin "18") (pinfunction "(ADC9/ACMP3/AMP1+/PCINT13)PC5_18") (pintype "bidirectional"))
    )
    (net (code "53") (name "unconnected-(U$1-(ADC10{slash}ACMP1{slash}PCINT14)PC6-Pad22)") (class "Default")
      (node (ref "U$1") (pin "22") (pinfunction "(ADC10/ACMP1/PCINT14)PC6_22") (pintype "bidirectional"))
    )
    (net (code "54") (name "unconnected-(U$1-(AMP0+{slash}PCINT4)PB4-Pad24)") (class "Default")
      (node (ref "U$1") (pin "24") (pinfunction "(AMP0+/PCINT4)PB4_24") (pintype "bidirectional"))
    )
    (net (code "55") (name "unconnected-(U$1-(D2A{slash}AMP2+{slash}PCINT15)PC7-Pad25)") (class "Default")
      (node (ref "U$1") (pin "25") (pinfunction "(D2A/AMP2+/PCINT15)PC7_25") (pintype "bidirectional"))
    )
    (net (code "56") (name "unconnected-(U$1-(PCINT8{slash}INT3{slash}PSCOUT1A)PC0-Pad30)") (class "Default")
      (node (ref "U$1") (pin "30") (pinfunction "(PCINT8/INT3/PSCOUT1A)PC0_30") (pintype "bidirectional"))
    )
    (net (code "57") (name "unconnected-(U$1-(PCINT9{slash}PSCIN1{slash}OC1B{slash}SS_A)PC1-Pad3)") (class "Default")
      (node (ref "U$1") (pin "3") (pinfunction "(PCINT9/PSCIN1/OC1B/SS_A)PC1_3") (pintype "bidirectional"))
    )
    (net (code "58") (name "unconnected-(U$1-(PCINT16{slash}PSCOUT0A)PD0-Pad29)") (class "Default")
      (node (ref "U$1") (pin "29") (pinfunction "(PCINT16/PSCOUT0A)PD0_29") (pintype "bidirectional"))
    )
    (net (code "59") (name "unconnected-(U$1-(PCINT17{slash}PSCIN0{slash}CLKO)PD1-Pad32)") (class "Default")
      (node (ref "U$1") (pin "32") (pinfunction "(PCINT17/PSCIN0/CLKO)PD1_32") (pintype "bidirectional"))
    )
    (net (code "60") (name "unconnected-(U$2-A1-Pad2)") (class "Default")
      (node (ref "U$2") (pin "2") (pinfunction "A1_2") (pintype "bidirectional"))
    )
    (net (code "61") (name "unconnected-(U$5-NC-Pad4)") (class "Default")
      (node (ref "U$5") (pin "4") (pinfunction "NC_4") (pintype "bidirectional"))
    )
    (net (code "62") (name "unconnected-(X7-Pad1)") (class "Default")
      (node (ref "X7") (pin "1") (pinfunction "1_1") (pintype "passive"))
    )
    (net (code "63") (name "unconnected-(X7-Pad4)") (class "Default")
      (node (ref "X7") (pin "4") (pinfunction "4_4") (pintype "passive"))
    )
    (net (code "64") (name "unconnected-(X7-Pad8)") (class "Default")
      (node (ref "X7") (pin "8") (pinfunction "8_8") (pintype "passive"))
    )
  )
)
